# WSTL18P2.net
KiCad netlist of a schematic drawn in EAGLE
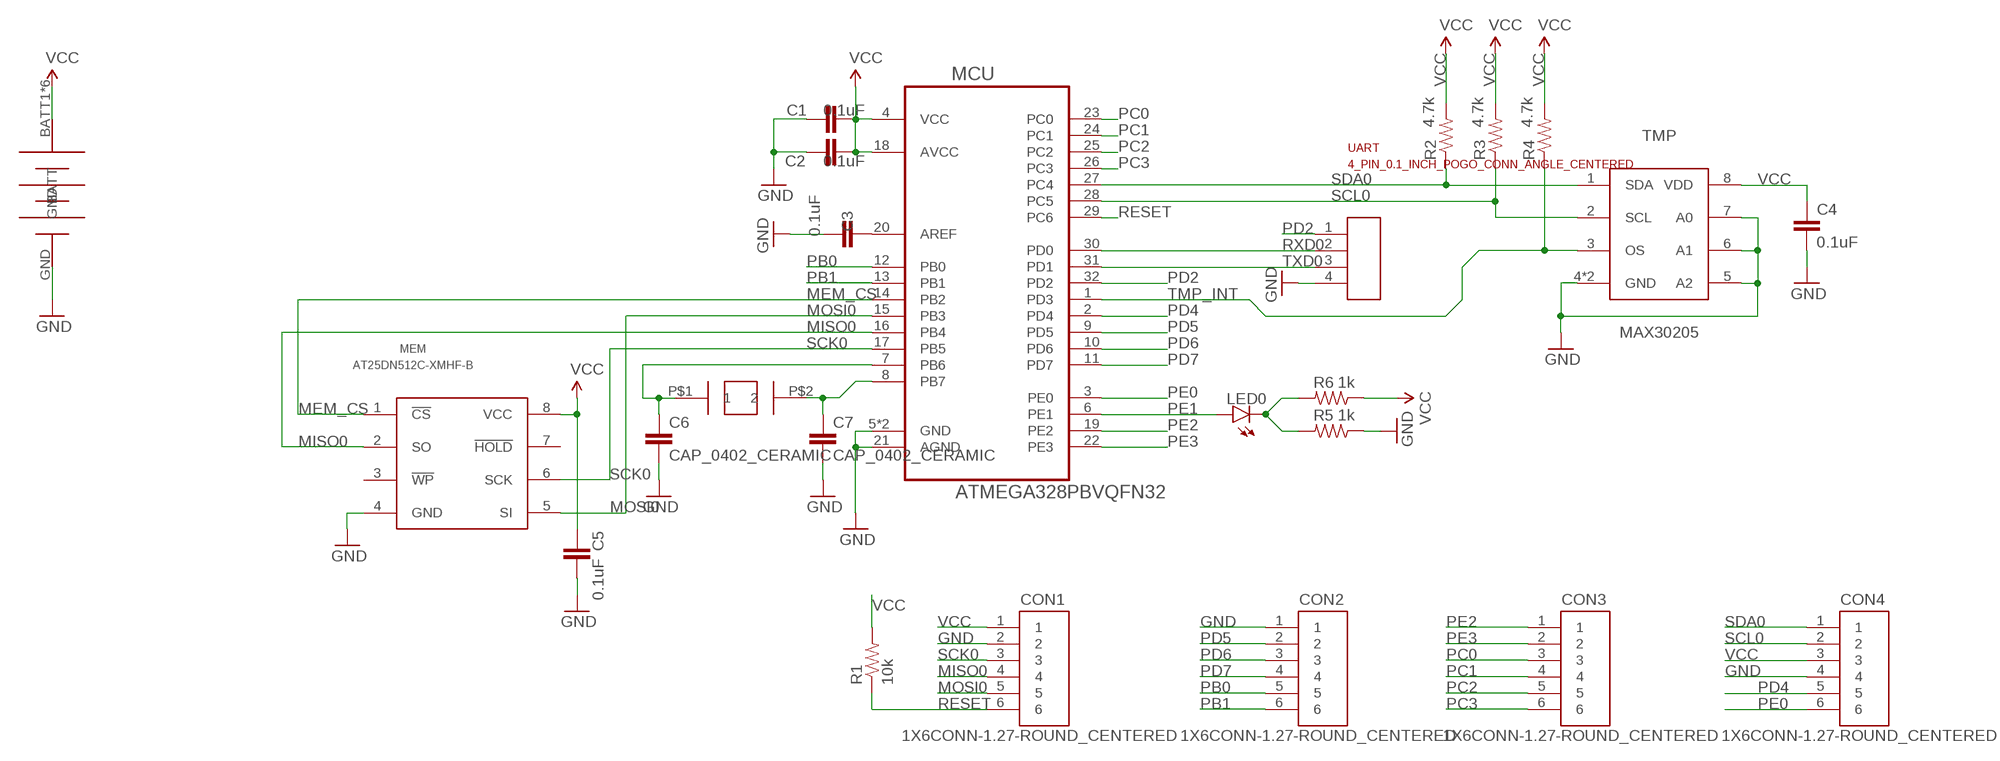
[diagram p0: schematic, sheet 1]

(export (version "E")
  (design (tool "Eeschema 10.0.6"))
  (components
    (comp (ref "C1")
      (value "0.1uF")
      (footprint "eagle-import:SMD_0402")
      (libsource (lib "eagle-import") (part "CAP_0402"))
    )
    (comp (ref "C2")
      (value "0.1uF")
      (footprint "eagle-import:SMD_0402")
      (libsource (lib "eagle-import") (part "CAP_0402"))
    )
    (comp (ref "C3")
      (value "0.1uF")
      (footprint "eagle-import:SMD_0402")
      (libsource (lib "eagle-import") (part "CAP_0402"))
    )
    (comp (ref "C4")
      (value "0.1uF")
      (footprint "eagle-import:CAP_0402")
      (libsource (lib "eagle-import") (part "CAP_0402_CERAMIC"))
    )
    (comp (ref "C5")
      (value "0.1uF")
      (footprint "eagle-import:CAP_0402")
      (libsource (lib "eagle-import") (part "CAP_0402_CERAMIC"))
    )
    (comp (ref "C6")
      (value "CAP_0402_CERAMIC")
      (footprint "eagle-import:CAP_0402")
      (libsource (lib "eagle-import") (part "CAP_0402_CERAMIC"))
    )
    (comp (ref "C7")
      (value "CAP_0402_CERAMIC")
      (footprint "eagle-import:CAP_0402")
      (libsource (lib "eagle-import") (part "CAP_0402_CERAMIC"))
    )
    (comp (ref "CON1")
      (value "1X6CONN-1.27-ROUND_CENTERED")
      (footprint "eagle-import:1X6_1.27_ROUND_CENTERED")
      (libsource (lib "eagle-import") (part "1X6CONN-1.27-ROUND_CENTERED"))
    )
    (comp (ref "CON2")
      (value "1X6CONN-1.27-ROUND_CENTERED")
      (footprint "eagle-import:1X6_1.27_ROUND_CENTERED")
      (libsource (lib "eagle-import") (part "1X6CONN-1.27-ROUND_CENTERED"))
    )
    (comp (ref "CON3")
      (value "1X6CONN-1.27-ROUND_CENTERED")
      (footprint "eagle-import:1X6_1.27_ROUND_CENTERED")
      (libsource (lib "eagle-import") (part "1X6CONN-1.27-ROUND_CENTERED"))
    )
    (comp (ref "CON4")
      (value "1X6CONN-1.27-ROUND_CENTERED")
      (footprint "eagle-import:1X6_1.27_ROUND_CENTERED")
      (libsource (lib "eagle-import") (part "1X6CONN-1.27-ROUND_CENTERED"))
    )
    (comp (ref "LED0")
      (value "LED_0402")
      (footprint "eagle-import:LED_0402")
      (libsource (lib "eagle-import") (part "LED_0402"))
    )
    (comp (ref "MCU")
      (value "ATMEGA328PBVQFN32")
      (footprint "eagle-import:ATMEGA328PB_VFQFN32")
      (libsource (lib "eagle-import") (part "ATMEGA328PBVQFN32"))
    )
    (comp (ref "MEM")
      (value "AT25DN512C-XMHF-B")
      (footprint "eagle-import:TSSSOP-8")
      (libsource (lib "eagle-import") (part "AT25DN512C-XMHF-B"))
    )
    (comp (ref "R1")
      (value "10k")
      (footprint "eagle-import:RES_0402")
      (libsource (lib "eagle-import") (part "RES_0402_CERAMIC"))
    )
    (comp (ref "R2")
      (value "4.7k")
      (footprint "eagle-import:RES_0402")
      (libsource (lib "eagle-import") (part "RES_0402_CERAMIC"))
    )
    (comp (ref "R3")
      (value "4.7k")
      (footprint "eagle-import:RES_0402")
      (libsource (lib "eagle-import") (part "RES_0402_CERAMIC"))
    )
    (comp (ref "R4")
      (value "4.7k")
      (footprint "eagle-import:RES_0402")
      (libsource (lib "eagle-import") (part "RES_0402_CERAMIC"))
    )
    (comp (ref "R5")
      (value "1k")
      (footprint "eagle-import:RES_0402")
      (libsource (lib "eagle-import") (part "RES_0402_CERAMIC"))
    )
    (comp (ref "R6")
      (value "1k")
      (footprint "eagle-import:RES_0402")
      (libsource (lib "eagle-import") (part "RES_0402_CERAMIC"))
    )
    (comp (ref "T1")
      (value "ABS07AIG")
      (footprint "eagle-import:ABS07AIG")
      (libsource (lib "eagle-import") (part "ABS07AIG"))
    )
    (comp (ref "TMP")
      (value "MAX30205")
      (footprint "eagle-import:MAX30205_TDFN8")
      (libsource (lib "eagle-import") (part "MAX30205"))
    )
    (comp (ref "U$1")
      (value "LINX-CR2032-BAT-HLD-M-THM")
      (footprint "eagle-import:CR2032-LINX-M-THM")
      (libsource (lib "eagle-import") (part "LINX-CR2032-BAT-HLD-M-THM"))
    )
    (comp (ref "UART")
      (value "4_PIN_0.1_INCH_POGO_CONN_ANGLE_CENTERED")
      (footprint "eagle-import:4_PIN_0.1__POGO_ANGLE_CENTERED")
      (libsource (lib "eagle-import") (part "4_PIN_0.1_INCH_POGO_CONN_ANGLE_CENTERED"))
    )
  )
  (nets
    (net (code "1") (name "/MEM_CS") (class "Default")
      (node (ref "MCU") (pin "14") (pinfunction "PB2_14") (pintype "bidirectional"))
      (node (ref "MEM") (pin "1") (pinfunction "~{CS}_1") (pintype "bidirectional"))
    )
    (net (code "2") (name "/MISO0") (class "Default")
      (node (ref "CON1") (pin "4") (pinfunction "4_4") (pintype "bidirectional"))
      (node (ref "MCU") (pin "16") (pinfunction "PB4_16") (pintype "bidirectional"))
      (node (ref "MEM") (pin "2") (pinfunction "SO_2") (pintype "bidirectional"))
    )
    (net (code "3") (name "/MOSI0") (class "Default")
      (node (ref "CON1") (pin "5") (pinfunction "5_5") (pintype "bidirectional"))
      (node (ref "MCU") (pin "15") (pinfunction "PB3_15") (pintype "bidirectional"))
      (node (ref "MEM") (pin "5") (pinfunction "SI_5") (pintype "bidirectional"))
    )
    (net (code "4") (name "/PB0") (class "Default")
      (node (ref "CON2") (pin "5") (pinfunction "5_5") (pintype "bidirectional"))
      (node (ref "MCU") (pin "12") (pinfunction "PB0_12") (pintype "bidirectional"))
    )
    (net (code "5") (name "/PB1") (class "Default")
      (node (ref "CON2") (pin "6") (pinfunction "6_6") (pintype "bidirectional"))
      (node (ref "MCU") (pin "13") (pinfunction "PB1_13") (pintype "bidirectional"))
    )
    (net (code "6") (name "/PC0") (class "Default")
      (node (ref "CON3") (pin "3") (pinfunction "3_3") (pintype "bidirectional"))
      (node (ref "MCU") (pin "23") (pinfunction "PC0_23") (pintype "bidirectional"))
    )
    (net (code "7") (name "/PC1") (class "Default")
      (node (ref "CON3") (pin "4") (pinfunction "4_4") (pintype "bidirectional"))
      (node (ref "MCU") (pin "24") (pinfunction "PC1_24") (pintype "bidirectional"))
    )
    (net (code "8") (name "/PC2") (class "Default")
      (node (ref "CON3") (pin "5") (pinfunction "5_5") (pintype "bidirectional"))
      (node (ref "MCU") (pin "25") (pinfunction "PC2_25") (pintype "bidirectional"))
    )
    (net (code "9") (name "/PC3") (class "Default")
      (node (ref "CON3") (pin "6") (pinfunction "6_6") (pintype "bidirectional"))
      (node (ref "MCU") (pin "26") (pinfunction "PC3_26") (pintype "bidirectional"))
    )
    (net (code "10") (name "/PD2") (class "Default")
      (node (ref "MCU") (pin "32") (pinfunction "PD2_32") (pintype "bidirectional"))
      (node (ref "UART") (pin "1") (pinfunction "1_1") (pintype "bidirectional"))
    )
    (net (code "11") (name "/PD4") (class "Default")
      (node (ref "CON4") (pin "5") (pinfunction "5_5") (pintype "bidirectional"))
      (node (ref "MCU") (pin "2") (pinfunction "PD4_2") (pintype "bidirectional"))
    )
    (net (code "12") (name "/PD5") (class "Default")
      (node (ref "CON2") (pin "2") (pinfunction "2_2") (pintype "bidirectional"))
      (node (ref "MCU") (pin "9") (pinfunction "PD5_9") (pintype "bidirectional"))
    )
    (net (code "13") (name "/PD6") (class "Default")
      (node (ref "CON2") (pin "3") (pinfunction "3_3") (pintype "bidirectional"))
      (node (ref "MCU") (pin "10") (pinfunction "PD6_10") (pintype "bidirectional"))
    )
    (net (code "14") (name "/PD7") (class "Default")
      (node (ref "CON2") (pin "4") (pinfunction "4_4") (pintype "bidirectional"))
      (node (ref "MCU") (pin "11") (pinfunction "PD7_11") (pintype "bidirectional"))
    )
    (net (code "15") (name "/PE0") (class "Default")
      (node (ref "CON4") (pin "6") (pinfunction "6_6") (pintype "bidirectional"))
      (node (ref "MCU") (pin "3") (pinfunction "PE0_3") (pintype "bidirectional"))
    )
    (net (code "16") (name "/PE1") (class "Default")
      (node (ref "LED0") (pin "ANODE") (pinfunction "A_ANODE") (pintype "passive"))
      (node (ref "MCU") (pin "6") (pinfunction "PE1_6") (pintype "bidirectional"))
    )
    (net (code "17") (name "/PE2") (class "Default")
      (node (ref "CON3") (pin "1") (pinfunction "1_1") (pintype "bidirectional"))
      (node (ref "MCU") (pin "19") (pinfunction "PE2_19") (pintype "bidirectional"))
    )
    (net (code "18") (name "/PE3") (class "Default")
      (node (ref "CON3") (pin "2") (pinfunction "2_2") (pintype "bidirectional"))
      (node (ref "MCU") (pin "22") (pinfunction "PE3_22") (pintype "bidirectional"))
    )
    (net (code "19") (name "/RESET") (class "Default")
      (node (ref "CON1") (pin "6") (pinfunction "6_6") (pintype "bidirectional"))
      (node (ref "MCU") (pin "29") (pinfunction "PC6_29") (pintype "bidirectional"))
      (node (ref "R1") (pin "2") (pinfunction "2_2") (pintype "passive"))
    )
    (net (code "20") (name "/RXD0") (class "Default")
      (node (ref "MCU") (pin "30") (pinfunction "PD0_30") (pintype "bidirectional"))
      (node (ref "UART") (pin "2") (pinfunction "2_2") (pintype "bidirectional"))
    )
    (net (code "21") (name "/SCK0") (class "Default")
      (node (ref "CON1") (pin "3") (pinfunction "3_3") (pintype "bidirectional"))
      (node (ref "MCU") (pin "17") (pinfunction "PB5_17") (pintype "bidirectional"))
      (node (ref "MEM") (pin "6") (pinfunction "SCK_6") (pintype "bidirectional"))
    )
    (net (code "22") (name "/SCL0") (class "Default")
      (node (ref "CON4") (pin "2") (pinfunction "2_2") (pintype "bidirectional"))
      (node (ref "MCU") (pin "28") (pinfunction "PC5_28") (pintype "bidirectional"))
      (node (ref "R3") (pin "2") (pinfunction "2_2") (pintype "passive"))
      (node (ref "TMP") (pin "2") (pinfunction "SCL_2") (pintype "bidirectional"))
    )
    (net (code "23") (name "/SDA0") (class "Default")
      (node (ref "CON4") (pin "1") (pinfunction "1_1") (pintype "bidirectional"))
      (node (ref "MCU") (pin "27") (pinfunction "PC4_27") (pintype "bidirectional"))
      (node (ref "R2") (pin "2") (pinfunction "2_2") (pintype "passive"))
      (node (ref "TMP") (pin "1") (pinfunction "SDA_1") (pintype "bidirectional"))
    )
    (net (code "24") (name "/TMP_INT") (class "Default")
      (node (ref "MCU") (pin "1") (pinfunction "PD3_1") (pintype "bidirectional"))
      (node (ref "R4") (pin "2") (pinfunction "2_2") (pintype "passive"))
      (node (ref "TMP") (pin "3") (pinfunction "OS_3") (pintype "bidirectional"))
    )
    (net (code "25") (name "/TXD0") (class "Default")
      (node (ref "MCU") (pin "31") (pinfunction "PD1_31") (pintype "bidirectional"))
      (node (ref "UART") (pin "3") (pinfunction "3_3") (pintype "bidirectional"))
    )
    (net (code "26") (name "GND") (class "Default")
      (node (ref "C1") (pin "2") (pinfunction "2_2") (pintype "bidirectional"))
      (node (ref "C2") (pin "2") (pinfunction "2_2") (pintype "bidirectional"))
      (node (ref "C3") (pin "2") (pinfunction "2_2") (pintype "bidirectional"))
      (node (ref "C4") (pin "2") (pinfunction "2_2") (pintype "passive"))
      (node (ref "C5") (pin "2") (pinfunction "2_2") (pintype "passive"))
      (node (ref "C6") (pin "2") (pinfunction "2_2") (pintype "passive"))
      (node (ref "C7") (pin "2") (pinfunction "2_2") (pintype "passive"))
      (node (ref "CON1") (pin "2") (pinfunction "2_2") (pintype "bidirectional"))
      (node (ref "CON2") (pin "1") (pinfunction "1_1") (pintype "bidirectional"))
      (node (ref "CON4") (pin "4") (pinfunction "4_4") (pintype "bidirectional"))
      (node (ref "MCU") (pin "21") (pinfunction "AGND_21") (pintype "passive"))
      (node (ref "MCU") (pin "5") (pinfunction "GND_5") (pintype "passive"))
      (node (ref "MCU") (pin "PAD") (pinfunction "GND_PAD") (pintype "passive"))
      (node (ref "MEM") (pin "4") (pinfunction "GND_4") (pintype "bidirectional"))
      (node (ref "R5") (pin "2") (pinfunction "2_2") (pintype "passive"))
      (node (ref "TMP") (pin "4") (pinfunction "GND_4") (pintype "bidirectional"))
      (node (ref "TMP") (pin "5") (pinfunction "A2_5") (pintype "bidirectional"))
      (node (ref "TMP") (pin "6") (pinfunction "A1_6") (pintype "bidirectional"))
      (node (ref "TMP") (pin "7") (pinfunction "A0_7") (pintype "bidirectional"))
      (node (ref "TMP") (pin "PAD") (pinfunction "GND_PAD") (pintype "bidirectional"))
      (node (ref "U$1") (pin "GND") (pinfunction "GND_GND") (pintype "bidirectional"))
      (node (ref "UART") (pin "4") (pinfunction "4_4") (pintype "bidirectional"))
    )
    (net (code "27") (name "Net-(LED0-C)") (class "Default")
      (node (ref "LED0") (pin "CATHODE") (pinfunction "C_CATHODE") (pintype "passive"))
      (node (ref "R5") (pin "1") (pinfunction "1_1") (pintype "passive"))
      (node (ref "R6") (pin "1") (pinfunction "1_1") (pintype "passive"))
    )
    (net (code "28") (name "Net-(MCU-AREF)") (class "Default")
      (node (ref "C3") (pin "1") (pinfunction "1_1") (pintype "bidirectional"))
      (node (ref "MCU") (pin "20") (pinfunction "AREF_20") (pintype "input"))
    )
    (net (code "29") (name "Net-(MCU-PB6)") (class "Default")
      (node (ref "C6") (pin "1") (pinfunction "1_1") (pintype "passive"))
      (node (ref "MCU") (pin "7") (pinfunction "PB6_7") (pintype "bidirectional"))
      (node (ref "T1") (pin "P$1") (pinfunction "1_P$1") (pintype "bidirectional"))
    )
    (net (code "30") (name "Net-(MCU-PB7)") (class "Default")
      (node (ref "C7") (pin "1") (pinfunction "1_1") (pintype "passive"))
      (node (ref "MCU") (pin "8") (pinfunction "PB7_8") (pintype "bidirectional"))
      (node (ref "T1") (pin "P$2") (pinfunction "2_P$2") (pintype "bidirectional"))
    )
    (net (code "31") (name "VCC") (class "Default")
      (node (ref "C1") (pin "1") (pinfunction "1_1") (pintype "bidirectional"))
      (node (ref "C2") (pin "1") (pinfunction "1_1") (pintype "bidirectional"))
      (node (ref "C4") (pin "1") (pinfunction "1_1") (pintype "passive"))
      (node (ref "C5") (pin "1") (pinfunction "1_1") (pintype "passive"))
      (node (ref "CON1") (pin "1") (pinfunction "1_1") (pintype "bidirectional"))
      (node (ref "CON4") (pin "3") (pinfunction "3_3") (pintype "bidirectional"))
      (node (ref "MCU") (pin "18") (pinfunction "AVCC_18") (pintype "power_in"))
      (node (ref "MCU") (pin "4") (pinfunction "VCC_4") (pintype "power_in"))
      (node (ref "MEM") (pin "8") (pinfunction "VCC_8") (pintype "bidirectional"))
      (node (ref "R1") (pin "1") (pinfunction "1_1") (pintype "passive"))
      (node (ref "R2") (pin "1") (pinfunction "1_1") (pintype "passive"))
      (node (ref "R3") (pin "1") (pinfunction "1_1") (pintype "passive"))
      (node (ref "R4") (pin "1") (pinfunction "1_1") (pintype "passive"))
      (node (ref "R6") (pin "2") (pinfunction "2_2") (pintype "passive"))
      (node (ref "TMP") (pin "8") (pinfunction "VDD_8") (pintype "bidirectional"))
      (node (ref "U$1") (pin "BATT1") (pinfunction "BATT_BATT1") (pintype "bidirectional"))
      (node (ref "U$1") (pin "BATT2") (pinfunction "BATT_BATT2") (pintype "bidirectional"))
      (node (ref "U$1") (pin "BATT3") (pinfunction "BATT_BATT3") (pintype "bidirectional"))
      (node (ref "U$1") (pin "BATT4") (pinfunction "BATT_BATT4") (pintype "bidirectional"))
      (node (ref "U$1") (pin "BATT5") (pinfunction "BATT_BATT5") (pintype "bidirectional"))
      (node (ref "U$1") (pin "BATT6") (pinfunction "BATT_BATT6") (pintype "bidirectional"))
    )
    (net (code "32") (name "unconnected-(MEM-~{HOLD}-Pad7)") (class "Default")
      (node (ref "MEM") (pin "7") (pinfunction "~{HOLD}_7") (pintype "bidirectional"))
    )
    (net (code "33") (name "unconnected-(MEM-~{WP}-Pad3)") (class "Default")
      (node (ref "MEM") (pin "3") (pinfunction "~{WP}_3") (pintype "bidirectional"))
    )
  )
)
